# DPPXHK_USB_SD_DEBUG.net
KiCad netlist of a schematic drawn in Altium Designer
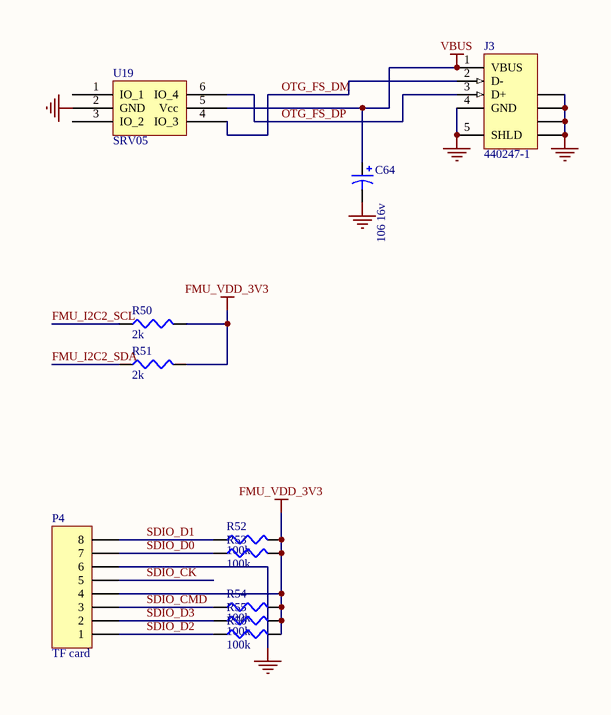
[diagram p0: DPPXHK_USB_SD_DEBUG.SCHDOC]

(export (version "E")
  (design (tool "Eeschema 10.0.6"))
  (components
    (comp (ref "C64")
      (value "106 16v")
      (footprint "LC0402")
      (description "Polarized Capacitor (Surface Mount)")
      (fields (field (name "PUBLISHER") "Altium Limited"))
      (libsource (lib "Miscellaneous Devices") (part "Cap Pol3"))
    )
    (comp (ref "J3")
      (value "440247-1")
      (footprint "MCRO_USB")
      (description "USB 2.0, Right Angle, SMT, B Type, Receptacle, 5 Position, Black")
      (fields (field (name "PUBLISHER") "Altium Limited"))
      (libsource (lib "AMP Serial Bus USB") (part "440247-1"))
    )
    (comp (ref "P4")
      (value "TF card")
      (footprint "TF-2")
      (description "Header, 8-Pin")
      (fields (field (name "PUBLISHER") "Altium Limited"))
      (libsource (lib "Miscellaneous Connectors") (part "Header 8"))
    )
    (comp (ref "R50")
      (value "2k")
      (footprint "0402R")
      (description "Resistor")
      (fields (field (name "PUBLISHER") "Altium Limited"))
      (libsource (lib "Miscellaneous Devices") (part "Res3"))
    )
    (comp (ref "R51")
      (value "2k")
      (footprint "0402R")
      (description "Resistor")
      (fields (field (name "PUBLISHER") "Altium Limited"))
      (libsource (lib "Miscellaneous Devices") (part "Res3"))
    )
    (comp (ref "R52")
      (value "100k")
      (footprint "0402R")
      (description "Resistor")
      (fields (field (name "PUBLISHER") "Altium Limited"))
      (libsource (lib "Miscellaneous Devices") (part "Res3"))
    )
    (comp (ref "R53")
      (value "100k")
      (footprint "0402R")
      (description "Resistor")
      (fields (field (name "PUBLISHER") "Altium Limited"))
      (libsource (lib "Miscellaneous Devices") (part "Res3"))
    )
    (comp (ref "R54")
      (value "100k")
      (footprint "0402R")
      (description "Resistor")
      (fields (field (name "PUBLISHER") "Altium Limited"))
      (libsource (lib "Miscellaneous Devices") (part "Res3"))
    )
    (comp (ref "R55")
      (value "100k")
      (footprint "0402R")
      (description "Resistor")
      (fields (field (name "PUBLISHER") "Altium Limited"))
      (libsource (lib "Miscellaneous Devices") (part "Res3"))
    )
    (comp (ref "R56")
      (value "100k")
      (footprint "0402R")
      (description "Resistor")
      (fields (field (name "PUBLISHER") "Altium Limited"))
      (libsource (lib "Miscellaneous Devices") (part "Res3"))
    )
    (comp (ref "U19") (value "SRV05") (footprint "SOT23-6") (libsource (lib "FCv3_20101224") (part "SRV05")))
  )
  (nets
    (net (code "1") (name "/FMU_I2C2_SCL") (class "Default")
      (node (ref "R50") (pin "1") (pinfunction "1_1") (pintype "passive"))
    )
    (net (code "2") (name "/FMU_I2C2_SDA") (class "Default")
      (node (ref "R51") (pin "1") (pinfunction "1_1") (pintype "passive"))
    )
    (net (code "3") (name "/OTG_FS_DM") (class "Default")
      (node (ref "J3") (pin "2") (pinfunction "D-_2") (pintype "input"))
      (node (ref "U19") (pin "4") (pinfunction "IO_3_4") (pintype "passive"))
    )
    (net (code "4") (name "/OTG_FS_DP") (class "Default")
      (node (ref "J3") (pin "3") (pinfunction "D+_3") (pintype "input"))
      (node (ref "U19") (pin "6") (pinfunction "IO_4_6") (pintype "passive"))
    )
    (net (code "5") (name "/SDIO_CK") (class "Default")
      (node (ref "P4") (pin "5") (pinfunction "5_5") (pintype "passive"))
    )
    (net (code "6") (name "/SDIO_CMD") (class "Default")
      (node (ref "P4") (pin "3") (pinfunction "3_3") (pintype "passive"))
      (node (ref "R54") (pin "1") (pinfunction "1_1") (pintype "passive"))
    )
    (net (code "7") (name "/SDIO_D0") (class "Default")
      (node (ref "P4") (pin "7") (pinfunction "7_7") (pintype "passive"))
      (node (ref "R53") (pin "1") (pinfunction "1_1") (pintype "passive"))
    )
    (net (code "8") (name "/SDIO_D1") (class "Default")
      (node (ref "P4") (pin "8") (pinfunction "8_8") (pintype "passive"))
      (node (ref "R52") (pin "1") (pinfunction "1_1") (pintype "passive"))
    )
    (net (code "9") (name "/SDIO_D2") (class "Default")
      (node (ref "P4") (pin "1") (pinfunction "1_1") (pintype "passive"))
      (node (ref "R56") (pin "1") (pinfunction "1_1") (pintype "passive"))
    )
    (net (code "10") (name "/SDIO_D3") (class "Default")
      (node (ref "P4") (pin "2") (pinfunction "2_2") (pintype "passive"))
      (node (ref "R55") (pin "1") (pinfunction "1_1") (pintype "passive"))
    )
    (net (code "11") (name "FMU_VDD_3V3") (class "Default")
      (node (ref "P4") (pin "4") (pinfunction "4_4") (pintype "passive"))
      (node (ref "R50") (pin "2") (pinfunction "2_2") (pintype "passive"))
      (node (ref "R51") (pin "2") (pinfunction "2_2") (pintype "passive"))
      (node (ref "R52") (pin "2") (pinfunction "2_2") (pintype "passive"))
      (node (ref "R53") (pin "2") (pinfunction "2_2") (pintype "passive"))
      (node (ref "R54") (pin "2") (pinfunction "2_2") (pintype "passive"))
      (node (ref "R55") (pin "2") (pinfunction "2_2") (pintype "passive"))
      (node (ref "R56") (pin "2") (pinfunction "2_2") (pintype "passive"))
    )
    (net (code "12") (name "GND") (class "Default")
      (node (ref "C64") (pin "2") (pinfunction "2_2") (pintype "passive"))
      (node (ref "J3") (pin "4") (pinfunction "GND_4") (pintype "power_in"))
      (node (ref "J3") (pin "5") (pinfunction "SHLD_5") (pintype "passive"))
      (node (ref "J3") (pin "6") (pinfunction "SHLD_6") (pintype "passive"))
      (node (ref "J3") (pin "7") (pinfunction "SHLD_7") (pintype "passive"))
      (node (ref "J3") (pin "8") (pinfunction "SHLD_8") (pintype "passive"))
      (node (ref "J3") (pin "9") (pinfunction "SHLD_9") (pintype "passive"))
      (node (ref "P4") (pin "6") (pinfunction "6_6") (pintype "passive"))
      (node (ref "U19") (pin "2") (pinfunction "GND_2") (pintype "passive"))
    )
    (net (code "13") (name "VBUS") (class "Default")
      (node (ref "C64") (pin "1") (pinfunction "1_1") (pintype "passive"))
      (node (ref "J3") (pin "1") (pinfunction "VBUS_1") (pintype "power_in"))
      (node (ref "U19") (pin "5") (pinfunction "Vcc_5") (pintype "passive"))
    )
    (net (code "14") (name "unconnected-(U19-IO_1-Pad1)") (class "Default")
      (node (ref "U19") (pin "1") (pinfunction "IO_1_1") (pintype "passive"))
    )
    (net (code "15") (name "unconnected-(U19-IO_2-Pad3)") (class "Default")
      (node (ref "U19") (pin "3") (pinfunction "IO_2_3") (pintype "passive"))
    )
  )
)
